# lc_meter.net
KiCad netlist of a schematic drawn in EAGLE
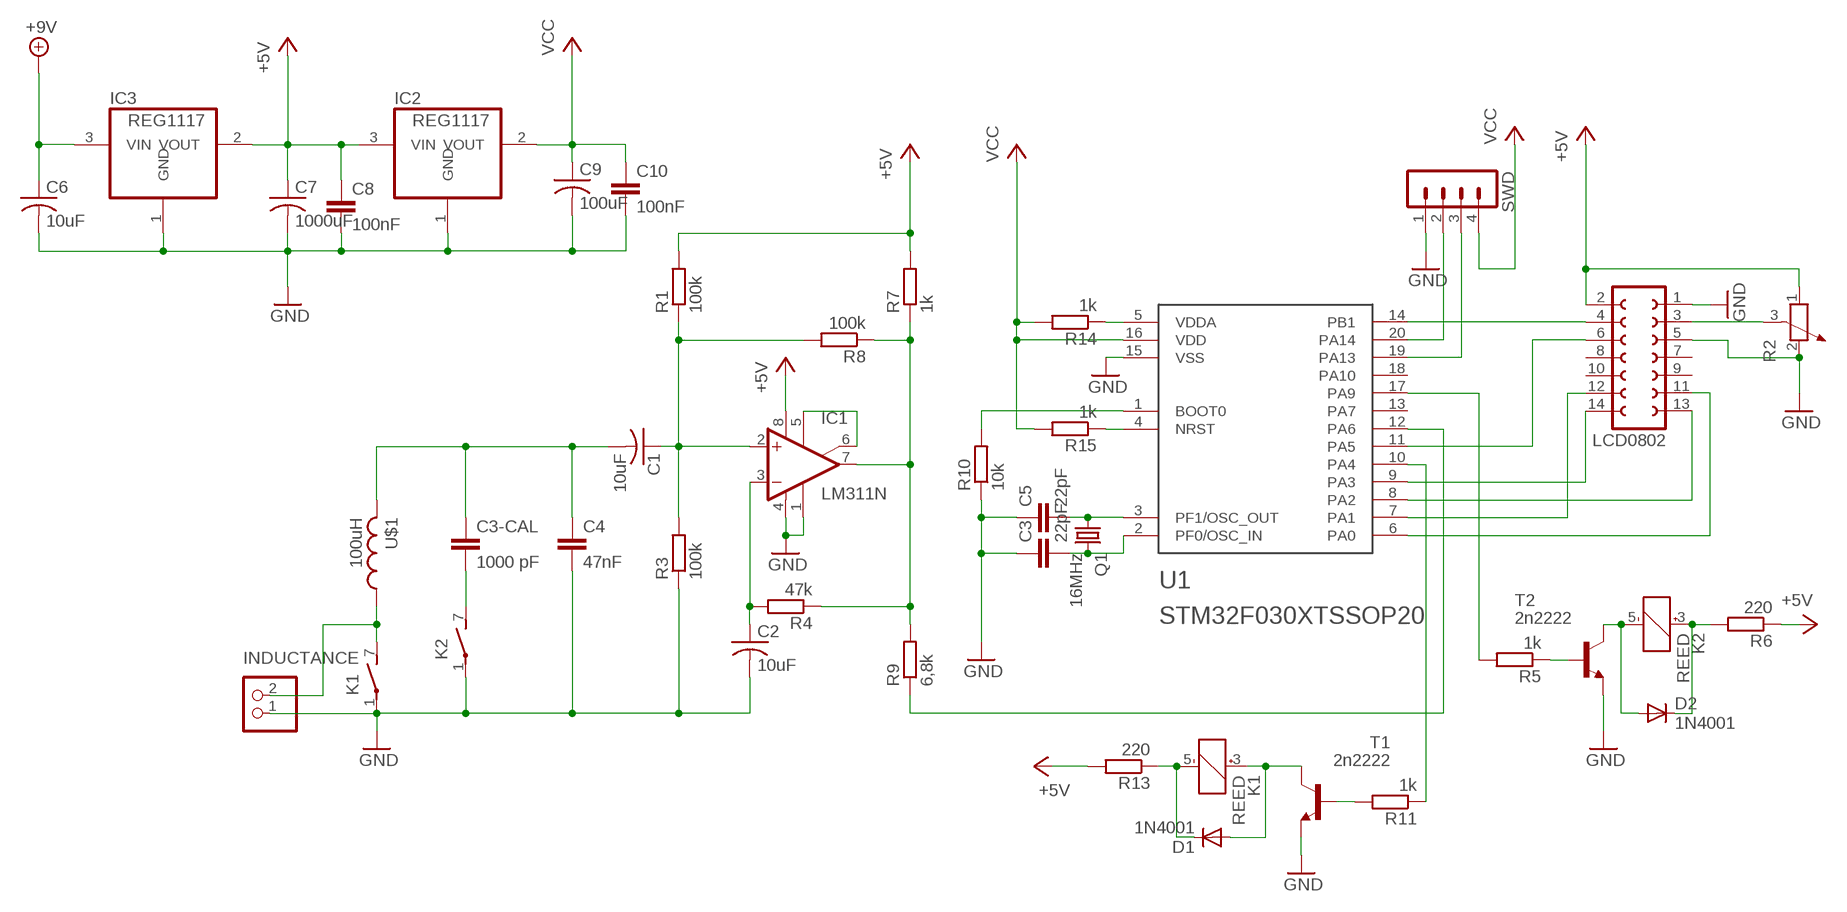
[diagram p0: schematic, sheet 1]

(export (version "E")
  (design (tool "Eeschema 10.0.6"))
  (components
    (comp (ref "C1")
      (value "10uF")
      (footprint "eagle-import:C025-024X044")
      (libsource (lib "eagle-import") (part "C-US025-024X044"))
    )
    (comp (ref "C2")
      (value "10uF")
      (footprint "eagle-import:C025-024X044")
      (libsource (lib "eagle-import") (part "C-US025-024X044"))
    )
    (comp (ref "C3")
      (value "22pF")
      (footprint "eagle-import:C2.5-3")
      (libsource (lib "eagle-import") (part "C2,5-3"))
    )
    (comp (ref "C3-CAL")
      (value "1000 pF")
      (footprint "eagle-import:C2.5-3")
      (libsource (lib "eagle-import") (part "C2,5-3"))
    )
    (comp (ref "C4")
      (value "47nF")
      (footprint "eagle-import:C2.5-3")
      (libsource (lib "eagle-import") (part "C2,5-3"))
    )
    (comp (ref "C5")
      (value "22pF")
      (footprint "eagle-import:C2.5-3")
      (libsource (lib "eagle-import") (part "C2,5-3"))
    )
    (comp (ref "C6")
      (value "10uF")
      (footprint "eagle-import:C025-024X044")
      (libsource (lib "eagle-import") (part "C-US025-024X044"))
    )
    (comp (ref "C7")
      (value "1000uF")
      (footprint "eagle-import:C025-024X044")
      (libsource (lib "eagle-import") (part "C-US025-024X044"))
    )
    (comp (ref "C8")
      (value "100nF")
      (footprint "eagle-import:C2.5-3")
      (libsource (lib "eagle-import") (part "C2,5-3"))
    )
    (comp (ref "C9")
      (value "100uF")
      (footprint "eagle-import:C025-024X044")
      (libsource (lib "eagle-import") (part "C-US025-024X044"))
    )
    (comp (ref "C10")
      (value "100nF")
      (footprint "eagle-import:C2.5-3")
      (libsource (lib "eagle-import") (part "C2,5-3"))
    )
    (comp (ref "D1")
      (value "1N4001")
      (footprint "eagle-import:DO41-10")
      (libsource (lib "eagle-import") (part "1N4004"))
    )
    (comp (ref "D2")
      (value "1N4001")
      (footprint "eagle-import:DO41-10")
      (libsource (lib "eagle-import") (part "1N4004"))
    )
    (comp (ref "IC1")
      (value "LM311N")
      (footprint "eagle-import:DIL08")
      (libsource (lib "eagle-import") (part "LM311N"))
    )
    (comp (ref "IC2")
      (value "REG1117")
      (footprint "eagle-import:SOT223")
      (libsource (lib "eagle-import") (part "REG1117"))
    )
    (comp (ref "IC3")
      (value "REG1117")
      (footprint "eagle-import:SOT223")
      (libsource (lib "eagle-import") (part "REG1117"))
    )
    (comp (ref "INDUCTANCE")
      (value "PINHD-1X2")
      (footprint "eagle-import:1X02")
      (libsource (lib "eagle-import") (part "PINHD-1X2"))
    )
    (comp (ref "K1")
      (value "REED")
      (footprint "eagle-import:REED")
      (libsource (lib "eagle-import") (part "REED"))
    )
    (comp (ref "K2")
      (value "REED")
      (footprint "eagle-import:REED")
      (libsource (lib "eagle-import") (part "REED"))
    )
    (comp (ref "LCD0802")
      (value "FE07-2")
      (footprint "eagle-import:FE07-2")
      (libsource (lib "eagle-import") (part "FE07-2"))
    )
    (comp (ref "Q1")
      (value "16MHz")
      (footprint "eagle-import:HC18U-V")
      (libsource (lib "eagle-import") (part "CRYSTALHC18U-V"))
    )
    (comp (ref "R1")
      (value "100k")
      (footprint "eagle-import:0204_7")
      (libsource (lib "eagle-import") (part "R0204/7"))
    )
    (comp (ref "R2")
      (value "POTENTIOMETER_PT_SPIN")
      (footprint "eagle-import:PT-SPIN")
      (libsource (lib "eagle-import") (part "POTENTIOMETER_PT_SPIN"))
    )
    (comp (ref "R3")
      (value "100k")
      (footprint "eagle-import:0204_7")
      (libsource (lib "eagle-import") (part "R0204/7"))
    )
    (comp (ref "R4")
      (value "47k")
      (footprint "eagle-import:0204_7")
      (libsource (lib "eagle-import") (part "R0204/7"))
    )
    (comp (ref "R5")
      (value "1k")
      (footprint "eagle-import:0204_7")
      (libsource (lib "eagle-import") (part "R0204/7"))
    )
    (comp (ref "R6")
      (value "220")
      (footprint "eagle-import:0204_7")
      (libsource (lib "eagle-import") (part "R0204/7"))
    )
    (comp (ref "R7")
      (value "1k")
      (footprint "eagle-import:0204_7")
      (libsource (lib "eagle-import") (part "R0204/7"))
    )
    (comp (ref "R8")
      (value "100k")
      (footprint "eagle-import:0204_7")
      (libsource (lib "eagle-import") (part "R0204/7"))
    )
    (comp (ref "R9")
      (value "6,8k")
      (footprint "eagle-import:0204_7")
      (libsource (lib "eagle-import") (part "R0204/7"))
    )
    (comp (ref "R10")
      (value "10k")
      (footprint "eagle-import:0204_7")
      (libsource (lib "eagle-import") (part "R0204/7"))
    )
    (comp (ref "R11")
      (value "1k")
      (footprint "eagle-import:0204_7")
      (libsource (lib "eagle-import") (part "R0204/7"))
    )
    (comp (ref "R13")
      (value "220")
      (footprint "eagle-import:0204_7")
      (libsource (lib "eagle-import") (part "R0204/7"))
    )
    (comp (ref "R14")
      (value "1k")
      (footprint "eagle-import:0204_7")
      (libsource (lib "eagle-import") (part "R0204/7"))
    )
    (comp (ref "R15")
      (value "1k")
      (footprint "eagle-import:0204_7")
      (libsource (lib "eagle-import") (part "R0204/7"))
    )
    (comp (ref "SWD")
      (value "MA04-1")
      (footprint "eagle-import:MA04-1")
      (libsource (lib "eagle-import") (part "MA04-1"))
    )
    (comp (ref "T1")
      (value "2n2222")
      (footprint "eagle-import:TO92-EBC")
      (libsource (lib "eagle-import") (part "-NPN-TO92-EBC2N2222"))
    )
    (comp (ref "T2")
      (value "2n2222")
      (footprint "eagle-import:TO92-EBC")
      (libsource (lib "eagle-import") (part "-NPN-TO92-EBC2N2222"))
    )
    (comp (ref "U$1")
      (value "100uH")
      (footprint "eagle-import:RESC0805_N")
      (libsource (lib "eagle-import") (part "INDUCTOR_0805_N"))
    )
    (comp (ref "U1")
      (value "STM32F030XTSSOP20")
      (footprint "eagle-import:TSSOP-20")
      (libsource (lib "eagle-import") (part "STM32F030XTSSOP20"))
    )
  )
  (nets
    (net (code "1") (name "+5V") (class "Default")
      (node (ref "C7") (pin "1") (pinfunction "1_1") (pintype "passive"))
      (node (ref "C8") (pin "1") (pinfunction "1_1") (pintype "passive"))
      (node (ref "IC1") (pin "8") (pinfunction "V+_8") (pintype "power_in"))
      (node (ref "IC2") (pin "3") (pinfunction "VIN_3") (pintype "input"))
      (node (ref "IC3") (pin "2") (pinfunction "VOUT_2") (pintype "output"))
      (node (ref "LCD0802") (pin "2") (pinfunction "2_2") (pintype "passive"))
      (node (ref "R1") (pin "2") (pinfunction "2_2") (pintype "passive"))
      (node (ref "R13") (pin "2") (pinfunction "2_2") (pintype "passive"))
      (node (ref "R2") (pin "1") (pinfunction "1_1") (pintype "passive"))
      (node (ref "R6") (pin "1") (pinfunction "1_1") (pintype "passive"))
      (node (ref "R7") (pin "2") (pinfunction "2_2") (pintype "passive"))
    )
    (net (code "2") (name "+9V") (class "Default")
      (node (ref "C6") (pin "1") (pinfunction "1_1") (pintype "passive"))
      (node (ref "IC3") (pin "3") (pinfunction "VIN_3") (pintype "input"))
    )
    (net (code "3") (name "GND") (class "Default")
      (node (ref "C10") (pin "2") (pinfunction "2_2") (pintype "passive"))
      (node (ref "C2") (pin "2") (pinfunction "2_2") (pintype "passive"))
      (node (ref "C3") (pin "1") (pinfunction "1_1") (pintype "passive"))
      (node (ref "C4") (pin "2") (pinfunction "2_2") (pintype "passive"))
      (node (ref "C5") (pin "1") (pinfunction "1_1") (pintype "passive"))
      (node (ref "C6") (pin "2") (pinfunction "2_2") (pintype "passive"))
      (node (ref "C7") (pin "2") (pinfunction "2_2") (pintype "passive"))
      (node (ref "C8") (pin "2") (pinfunction "2_2") (pintype "passive"))
      (node (ref "C9") (pin "2") (pinfunction "2_2") (pintype "passive"))
      (node (ref "IC1") (pin "1") (pinfunction "GND_1") (pintype "passive"))
      (node (ref "IC1") (pin "4") (pinfunction "V-_4") (pintype "power_in"))
      (node (ref "IC2") (pin "1") (pinfunction "GND_1") (pintype "power_in"))
      (node (ref "IC3") (pin "1") (pinfunction "GND_1") (pintype "power_in"))
      (node (ref "INDUCTANCE") (pin "1") (pinfunction "1_1") (pintype "passive"))
      (node (ref "K1") (pin "1") (pinfunction "P_1") (pintype "passive"))
      (node (ref "K2") (pin "1") (pinfunction "P_1") (pintype "passive"))
      (node (ref "LCD0802") (pin "1") (pinfunction "1_1") (pintype "passive"))
      (node (ref "LCD0802") (pin "5") (pinfunction "5_5") (pintype "passive"))
      (node (ref "R10") (pin "1") (pinfunction "1_1") (pintype "passive"))
      (node (ref "R2") (pin "2") (pinfunction "2_2") (pintype "passive"))
      (node (ref "R3") (pin "1") (pinfunction "1_1") (pintype "passive"))
      (node (ref "SWD") (pin "1") (pinfunction "1_1") (pintype "passive"))
      (node (ref "T1") (pin "E") (pinfunction "E_E") (pintype "passive"))
      (node (ref "T2") (pin "E") (pinfunction "E_E") (pintype "passive"))
      (node (ref "U1") (pin "15") (pinfunction "VSS_15") (pintype "bidirectional"))
    )
    (net (code "4") (name "Net-(C1-Pad2)") (class "Default")
      (node (ref "C1") (pin "2") (pinfunction "2_2") (pintype "passive"))
      (node (ref "C3-CAL") (pin "1") (pinfunction "1_1") (pintype "passive"))
      (node (ref "C4") (pin "1") (pinfunction "1_1") (pintype "passive"))
      (node (ref "U$1") (pin "2") (pinfunction "2_2") (pintype "passive"))
    )
    (net (code "5") (name "Net-(IC1-+IN)") (class "Default")
      (node (ref "C1") (pin "1") (pinfunction "1_1") (pintype "passive"))
      (node (ref "IC1") (pin "2") (pinfunction "+IN_2") (pintype "input"))
      (node (ref "R1") (pin "1") (pinfunction "1_1") (pintype "passive"))
      (node (ref "R3") (pin "2") (pinfunction "2_2") (pintype "passive"))
      (node (ref "R8") (pin "2") (pinfunction "2_2") (pintype "passive"))
    )
    (net (code "6") (name "Net-(IC1--IN)") (class "Default")
      (node (ref "C2") (pin "1") (pinfunction "1_1") (pintype "passive"))
      (node (ref "IC1") (pin "3") (pinfunction "-IN_3") (pintype "input"))
      (node (ref "R4") (pin "2") (pinfunction "2_2") (pintype "passive"))
    )
    (net (code "7") (name "Net-(IC1-ON)") (class "Default")
      (node (ref "IC1") (pin "5") (pinfunction "ON_5") (pintype "passive"))
      (node (ref "IC1") (pin "6") (pinfunction "ON/STR_6") (pintype "passive"))
    )
    (net (code "8") (name "Net-(IC1-OUT)") (class "Default")
      (node (ref "IC1") (pin "7") (pinfunction "OUT_7") (pintype "output"))
      (node (ref "R4") (pin "1") (pinfunction "1_1") (pintype "passive"))
      (node (ref "R7") (pin "1") (pinfunction "1_1") (pintype "passive"))
      (node (ref "R8") (pin "1") (pinfunction "1_1") (pintype "passive"))
      (node (ref "R9") (pin "2") (pinfunction "2_2") (pintype "passive"))
    )
    (net (code "9") (name "Net-(K1A-+)") (class "Default")
      (node (ref "D1") (pin "A") (pinfunction "A_A") (pintype "passive"))
      (node (ref "K1") (pin "3") (pinfunction "+_3") (pintype "passive"))
      (node (ref "T1") (pin "C") (pinfunction "C_C") (pintype "passive"))
    )
    (net (code "10") (name "Net-(K1A--)") (class "Default")
      (node (ref "D1") (pin "C") (pinfunction "C_C") (pintype "passive"))
      (node (ref "K1") (pin "5") (pinfunction "-_5") (pintype "passive"))
      (node (ref "R13") (pin "1") (pinfunction "1_1") (pintype "passive"))
    )
    (net (code "11") (name "Net-(K1B-S)") (class "Default")
      (node (ref "INDUCTANCE") (pin "2") (pinfunction "2_2") (pintype "passive"))
      (node (ref "K1") (pin "7") (pinfunction "S_7") (pintype "passive"))
      (node (ref "U$1") (pin "1") (pinfunction "1_1") (pintype "passive"))
    )
    (net (code "12") (name "Net-(K2A-+)") (class "Default")
      (node (ref "D2") (pin "C") (pinfunction "C_C") (pintype "passive"))
      (node (ref "K2") (pin "3") (pinfunction "+_3") (pintype "passive"))
      (node (ref "R6") (pin "2") (pinfunction "2_2") (pintype "passive"))
    )
    (net (code "13") (name "Net-(K2A--)") (class "Default")
      (node (ref "D2") (pin "A") (pinfunction "A_A") (pintype "passive"))
      (node (ref "K2") (pin "5") (pinfunction "-_5") (pintype "passive"))
      (node (ref "T2") (pin "C") (pinfunction "C_C") (pintype "passive"))
    )
    (net (code "14") (name "Net-(K2B-S)") (class "Default")
      (node (ref "C3-CAL") (pin "2") (pinfunction "2_2") (pintype "passive"))
      (node (ref "K2") (pin "7") (pinfunction "S_7") (pintype "passive"))
    )
    (net (code "15") (name "Net-(LCD0802-Pad3)") (class "Default")
      (node (ref "LCD0802") (pin "3") (pinfunction "3_3") (pintype "passive"))
      (node (ref "R2") (pin "3") (pinfunction "3_3") (pintype "passive"))
    )
    (net (code "16") (name "Net-(R5-Pad1)") (class "Default")
      (node (ref "R5") (pin "1") (pinfunction "1_1") (pintype "passive"))
      (node (ref "T2") (pin "B") (pinfunction "B_B") (pintype "passive"))
    )
    (net (code "17") (name "Net-(R11-Pad2)") (class "Default")
      (node (ref "R11") (pin "2") (pinfunction "2_2") (pintype "passive"))
      (node (ref "T1") (pin "B") (pinfunction "B_B") (pintype "passive"))
    )
    (net (code "18") (name "Net-(U1-BOOT0)") (class "Default")
      (node (ref "R10") (pin "2") (pinfunction "2_2") (pintype "passive"))
      (node (ref "U1") (pin "1") (pinfunction "BOOT0_1") (pintype "bidirectional"))
    )
    (net (code "19") (name "Net-(U1-NRST)") (class "Default")
      (node (ref "R15") (pin "1") (pinfunction "1_1") (pintype "passive"))
      (node (ref "U1") (pin "4") (pinfunction "NRST_4") (pintype "bidirectional"))
    )
    (net (code "20") (name "Net-(U1-PA0)") (class "Default")
      (node (ref "LCD0802") (pin "11") (pinfunction "11_11") (pintype "passive"))
      (node (ref "U1") (pin "6") (pinfunction "PA0_6") (pintype "bidirectional"))
    )
    (net (code "21") (name "Net-(U1-PA1)") (class "Default")
      (node (ref "LCD0802") (pin "12") (pinfunction "12_12") (pintype "passive"))
      (node (ref "U1") (pin "7") (pinfunction "PA1_7") (pintype "bidirectional"))
    )
    (net (code "22") (name "Net-(U1-PA2)") (class "Default")
      (node (ref "LCD0802") (pin "13") (pinfunction "13_13") (pintype "passive"))
      (node (ref "U1") (pin "8") (pinfunction "PA2_8") (pintype "bidirectional"))
    )
    (net (code "23") (name "Net-(U1-PA3)") (class "Default")
      (node (ref "LCD0802") (pin "14") (pinfunction "14_14") (pintype "passive"))
      (node (ref "U1") (pin "9") (pinfunction "PA3_9") (pintype "bidirectional"))
    )
    (net (code "24") (name "Net-(U1-PA4)") (class "Default")
      (node (ref "R11") (pin "1") (pinfunction "1_1") (pintype "passive"))
      (node (ref "U1") (pin "10") (pinfunction "PA4_10") (pintype "bidirectional"))
    )
    (net (code "25") (name "Net-(U1-PA5)") (class "Default")
      (node (ref "LCD0802") (pin "6") (pinfunction "6_6") (pintype "passive"))
      (node (ref "U1") (pin "11") (pinfunction "PA5_11") (pintype "bidirectional"))
    )
    (net (code "26") (name "Net-(U1-PA6)") (class "Default")
      (node (ref "R9") (pin "1") (pinfunction "1_1") (pintype "passive"))
      (node (ref "U1") (pin "12") (pinfunction "PA6_12") (pintype "bidirectional"))
    )
    (net (code "27") (name "Net-(U1-PA9)") (class "Default")
      (node (ref "R5") (pin "2") (pinfunction "2_2") (pintype "passive"))
      (node (ref "U1") (pin "17") (pinfunction "PA9_17") (pintype "bidirectional"))
    )
    (net (code "28") (name "Net-(U1-PA13)") (class "Default")
      (node (ref "SWD") (pin "3") (pinfunction "3_3") (pintype "passive"))
      (node (ref "U1") (pin "19") (pinfunction "PA13_19") (pintype "bidirectional"))
    )
    (net (code "29") (name "Net-(U1-PA14)") (class "Default")
      (node (ref "SWD") (pin "2") (pinfunction "2_2") (pintype "passive"))
      (node (ref "U1") (pin "20") (pinfunction "PA14_20") (pintype "bidirectional"))
    )
    (net (code "30") (name "Net-(U1-PB1)") (class "Default")
      (node (ref "LCD0802") (pin "4") (pinfunction "4_4") (pintype "passive"))
      (node (ref "U1") (pin "14") (pinfunction "PB1_14") (pintype "bidirectional"))
    )
    (net (code "31") (name "Net-(U1-PF0{slash}OSC_IN)") (class "Default")
      (node (ref "C3") (pin "2") (pinfunction "2_2") (pintype "passive"))
      (node (ref "Q1") (pin "2") (pinfunction "2_2") (pintype "passive"))
      (node (ref "U1") (pin "2") (pinfunction "PF0/OSC_IN_2") (pintype "bidirectional"))
    )
    (net (code "32") (name "Net-(U1-PF1{slash}OSC_OUT)") (class "Default")
      (node (ref "C5") (pin "2") (pinfunction "2_2") (pintype "passive"))
      (node (ref "Q1") (pin "1") (pinfunction "1_1") (pintype "passive"))
      (node (ref "U1") (pin "3") (pinfunction "PF1/OSC_OUT_3") (pintype "bidirectional"))
    )
    (net (code "33") (name "Net-(U1-VDDA)") (class "Default")
      (node (ref "R14") (pin "1") (pinfunction "1_1") (pintype "passive"))
      (node (ref "U1") (pin "5") (pinfunction "VDDA_5") (pintype "bidirectional"))
    )
    (net (code "34") (name "VCC") (class "Default")
      (node (ref "C10") (pin "1") (pinfunction "1_1") (pintype "passive"))
      (node (ref "C9") (pin "1") (pinfunction "1_1") (pintype "passive"))
      (node (ref "IC2") (pin "2") (pinfunction "VOUT_2") (pintype "output"))
      (node (ref "R14") (pin "2") (pinfunction "2_2") (pintype "passive"))
      (node (ref "R15") (pin "2") (pinfunction "2_2") (pintype "passive"))
      (node (ref "SWD") (pin "4") (pinfunction "4_4") (pintype "passive"))
      (node (ref "U1") (pin "16") (pinfunction "VDD_16") (pintype "bidirectional"))
    )
    (net (code "35") (name "unconnected-(LCD0802-Pad7)") (class "Default")
      (node (ref "LCD0802") (pin "7") (pinfunction "7_7") (pintype "passive"))
    )
    (net (code "36") (name "unconnected-(LCD0802-Pad8)") (class "Default")
      (node (ref "LCD0802") (pin "8") (pinfunction "8_8") (pintype "passive"))
    )
    (net (code "37") (name "unconnected-(LCD0802-Pad9)") (class "Default")
      (node (ref "LCD0802") (pin "9") (pinfunction "9_9") (pintype "passive"))
    )
    (net (code "38") (name "unconnected-(LCD0802-Pad10)") (class "Default")
      (node (ref "LCD0802") (pin "10") (pinfunction "10_10") (pintype "passive"))
    )
    (net (code "39") (name "unconnected-(U1-PA7-Pad13)") (class "Default")
      (node (ref "U1") (pin "13") (pinfunction "PA7_13") (pintype "bidirectional"))
    )
    (net (code "40") (name "unconnected-(U1-PA10-Pad18)") (class "Default")
      (node (ref "U1") (pin "18") (pinfunction "PA10_18") (pintype "bidirectional"))
    )
  )
)
